# Task1.net
KiCad netlist of a schematic drawn in Altium Designer
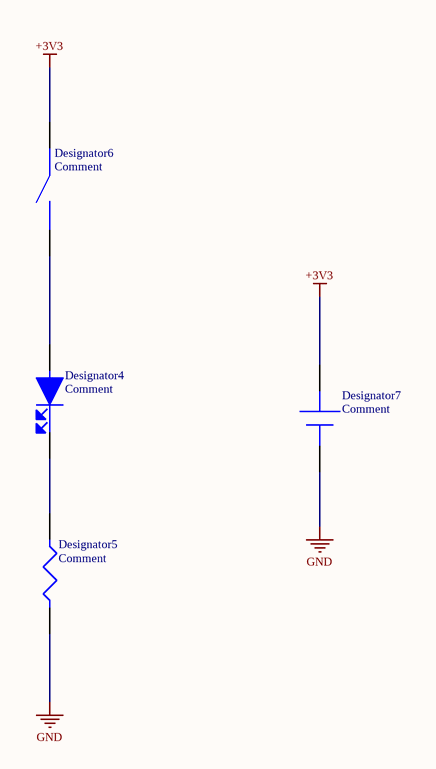
[diagram p0: Task1.SchDoc]

(export (version "E")
  (design (tool "Eeschema 10.0.6"))
  (components
    (comp (ref "Designator4")
      (value "Comment")
      (footprint "LED")
      (description "LED GREEN CLEAR 3528 SMD")
      (fields (field (name "PART NUMBER") "732-4997-1-ND"))
      (libsource (lib "Task-1") (part "LED"))
    )
    (comp (ref "Designator5")
      (value "Comment")
      (footprint "Resistor")
      (description "RES SMD 230OHM 0.01% 1/4W J LEAD")
      (fields (field (name "PART NUMBER") "Y1121230R000T9L-ND"))
      (libsource (lib "Task-1") (part "Resistor"))
    )
    (comp (ref "Designator6")
      (value "Comment")
      (footprint "Switch")
      (description "SWITCH TOGGLE SPDT 0.4VA 28V")
      (libsource (lib "Task-1") (part "Switch"))
    )
    (comp (ref "Designator7")
      (value "Comment")
      (footprint "Terminal")
      (description "Screw Terminals 3.5mm Pitch (2-Pin)")
      (fields (field (name "PART NUMBER") "PRT-08084 RoHS"))
      (libsource (lib "Integrated_Library1") (part "Terminal"))
    )
  )
  (nets
    (net (code "1") (name "+3V3") (class "Default")
      (node (ref "Designator6") (pin "1") (pinfunction "1_1") (pintype "passive"))
      (node (ref "Designator7") (pin "2") (pinfunction "2_2") (pintype "passive"))
    )
    (net (code "2") (name "GND") (class "Default")
      (node (ref "Designator5") (pin "2") (pinfunction "2_2") (pintype "passive"))
      (node (ref "Designator7") (pin "1") (pinfunction "1_1") (pintype "passive"))
    )
    (net (code "3") (name "Net-(Designator4-Pad1)") (class "Default")
      (node (ref "Designator4") (pin "1") (pinfunction "1_1") (pintype "passive"))
      (node (ref "Designator5") (pin "1") (pinfunction "1_1") (pintype "passive"))
    )
    (net (code "4") (name "Net-(Designator4-Pad2)") (class "Default")
      (node (ref "Designator4") (pin "2") (pinfunction "2_2") (pintype "passive"))
      (node (ref "Designator6") (pin "2") (pinfunction "2_2") (pintype "passive"))
    )
  )
)
